# ui_cpu.net
KiCad netlist of a schematic drawn in Altium Designer
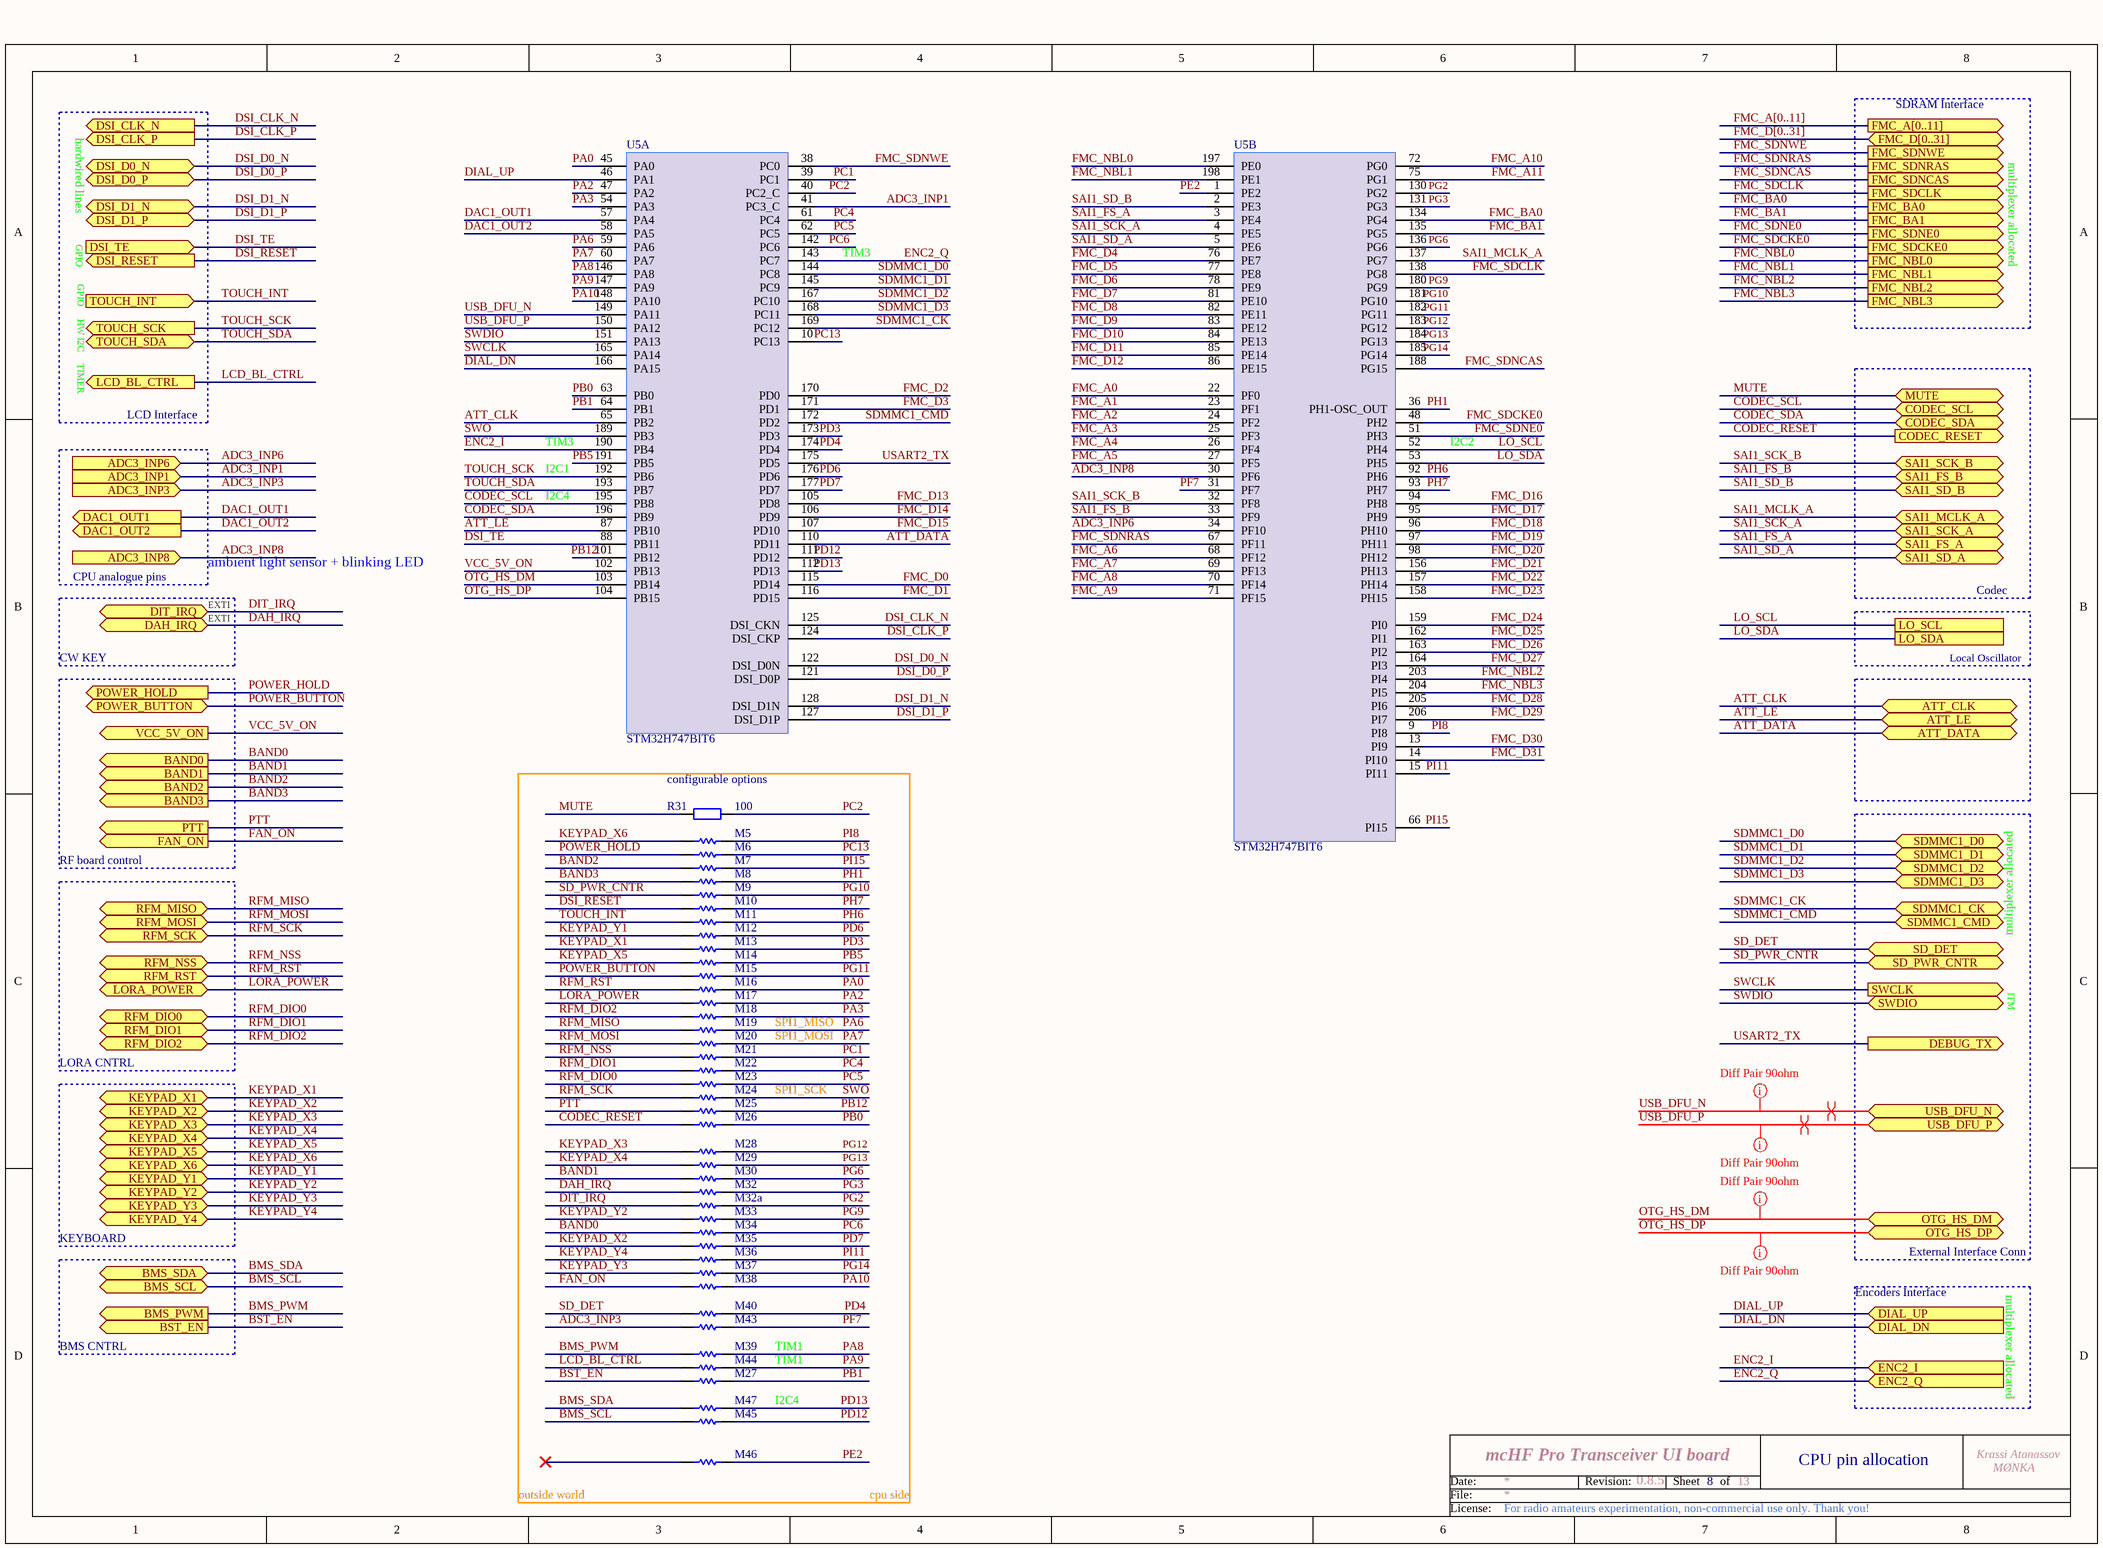
[diagram p0: ui_cpu.SchDoc]

(export (version "E")
  (design (tool "Eeschema 10.0.6"))
  (components
    (comp (ref "M5")
      (value "0")
      (footprint "SB_0603")
      (description "Link")
      (fields (field (name "PUBLISHER") "Altium Limited"))
      (libsource (lib "__ui") (part "Link"))
    )
    (comp (ref "M6")
      (value "0")
      (footprint "SB_0603")
      (description "Link")
      (fields (field (name "PUBLISHER") "Altium Limited"))
      (libsource (lib "__ui") (part "Link"))
    )
    (comp (ref "M7")
      (value "0")
      (footprint "SB_0603")
      (description "Link")
      (fields (field (name "PUBLISHER") "Altium Limited"))
      (libsource (lib "__ui") (part "Link"))
    )
    (comp (ref "M8")
      (value "0")
      (footprint "SB_0603")
      (description "Link")
      (fields (field (name "PUBLISHER") "Altium Limited"))
      (libsource (lib "__ui") (part "Link"))
    )
    (comp (ref "M9")
      (value "0")
      (footprint "SB_0603")
      (description "Link")
      (fields (field (name "PUBLISHER") "Altium Limited"))
      (libsource (lib "__ui") (part "Link"))
    )
    (comp (ref "M10")
      (value "0")
      (footprint "SB_0603")
      (description "Link")
      (fields (field (name "PUBLISHER") "Altium Limited"))
      (libsource (lib "__ui") (part "Link"))
    )
    (comp (ref "M11")
      (value "0")
      (footprint "SB_0603")
      (description "Link")
      (fields (field (name "PUBLISHER") "Altium Limited"))
      (libsource (lib "__ui") (part "Link"))
    )
    (comp (ref "M12")
      (value "0")
      (footprint "SB_0603")
      (description "Link")
      (fields (field (name "PUBLISHER") "Altium Limited"))
      (libsource (lib "__ui") (part "Link"))
    )
    (comp (ref "M13")
      (value "0")
      (footprint "SB_0603")
      (description "Link")
      (fields (field (name "PUBLISHER") "Altium Limited"))
      (libsource (lib "__ui") (part "Link"))
    )
    (comp (ref "M14")
      (value "0")
      (footprint "SB_0603")
      (description "Link")
      (fields (field (name "PUBLISHER") "Altium Limited"))
      (libsource (lib "__ui") (part "Link"))
    )
    (comp (ref "M15")
      (value "0")
      (footprint "SB_0603")
      (description "Link")
      (fields (field (name "PUBLISHER") "Altium Limited"))
      (libsource (lib "__ui") (part "Link"))
    )
    (comp (ref "M16")
      (value "0")
      (footprint "SB_0603")
      (description "Link")
      (fields (field (name "PUBLISHER") "Altium Limited"))
      (libsource (lib "__ui") (part "Link"))
    )
    (comp (ref "M17")
      (value "0")
      (footprint "SB_0603")
      (description "Link")
      (fields (field (name "PUBLISHER") "Altium Limited"))
      (libsource (lib "__ui") (part "Link"))
    )
    (comp (ref "M18")
      (value "0")
      (footprint "SB_0603")
      (description "Link")
      (fields (field (name "PUBLISHER") "Altium Limited"))
      (libsource (lib "__ui") (part "Link"))
    )
    (comp (ref "M19")
      (value "0")
      (footprint "SB_0603")
      (description "Link")
      (fields (field (name "PUBLISHER") "Altium Limited"))
      (libsource (lib "__ui") (part "Link"))
    )
    (comp (ref "M20")
      (value "0")
      (footprint "SB_0603")
      (description "Link")
      (fields (field (name "PUBLISHER") "Altium Limited"))
      (libsource (lib "__ui") (part "Link"))
    )
    (comp (ref "M21")
      (value "0")
      (footprint "SB_0603")
      (description "Link")
      (fields (field (name "PUBLISHER") "Altium Limited"))
      (libsource (lib "__ui") (part "Link"))
    )
    (comp (ref "M22")
      (value "0")
      (footprint "SB_0603")
      (description "Link")
      (fields (field (name "PUBLISHER") "Altium Limited"))
      (libsource (lib "__ui") (part "Link"))
    )
    (comp (ref "M23")
      (value "0")
      (footprint "SB_0603")
      (description "Link")
      (fields (field (name "PUBLISHER") "Altium Limited"))
      (libsource (lib "__ui") (part "Link"))
    )
    (comp (ref "M24")
      (value "0")
      (footprint "SB_0603")
      (description "Link")
      (fields (field (name "PUBLISHER") "Altium Limited"))
      (libsource (lib "__ui") (part "Link"))
    )
    (comp (ref "M25")
      (value "0")
      (footprint "SB_0603")
      (description "Link")
      (fields (field (name "PUBLISHER") "Altium Limited"))
      (libsource (lib "__ui") (part "Link"))
    )
    (comp (ref "M26")
      (value "0")
      (footprint "SB_0603")
      (description "Link")
      (fields (field (name "PUBLISHER") "Altium Limited"))
      (libsource (lib "__ui") (part "Link"))
    )
    (comp (ref "M27")
      (value "0")
      (footprint "SB_0603")
      (description "Link")
      (fields (field (name "PUBLISHER") "Altium Limited"))
      (libsource (lib "__ui") (part "Link"))
    )
    (comp (ref "M28")
      (value "0")
      (footprint "SB_0603")
      (description "Link")
      (fields (field (name "PUBLISHER") "Altium Limited"))
      (libsource (lib "__ui") (part "Link"))
    )
    (comp (ref "M29")
      (value "0")
      (footprint "SB_0603")
      (description "Link")
      (fields (field (name "PUBLISHER") "Altium Limited"))
      (libsource (lib "__ui") (part "Link"))
    )
    (comp (ref "M30")
      (value "0")
      (footprint "SB_0603")
      (description "Link")
      (fields (field (name "PUBLISHER") "Altium Limited"))
      (libsource (lib "__ui") (part "Link"))
    )
    (comp (ref "M32")
      (value "0")
      (footprint "SB_0603")
      (description "Link")
      (fields (field (name "PUBLISHER") "Altium Limited"))
      (libsource (lib "__ui") (part "Link"))
    )
    (comp (ref "M32a")
      (value "0")
      (footprint "SB_0603")
      (description "Link")
      (fields (field (name "PUBLISHER") "Altium Limited"))
      (libsource (lib "__ui") (part "Link"))
    )
    (comp (ref "M33")
      (value "0")
      (footprint "SB_0603")
      (description "Link")
      (fields (field (name "PUBLISHER") "Altium Limited"))
      (libsource (lib "__ui") (part "Link"))
    )
    (comp (ref "M34")
      (value "0")
      (footprint "SB_0603")
      (description "Link")
      (fields (field (name "PUBLISHER") "Altium Limited"))
      (libsource (lib "__ui") (part "Link"))
    )
    (comp (ref "M35")
      (value "0")
      (footprint "SB_0603")
      (description "Link")
      (fields (field (name "PUBLISHER") "Altium Limited"))
      (libsource (lib "__ui") (part "Link"))
    )
    (comp (ref "M36")
      (value "0")
      (footprint "SB_0603")
      (description "Link")
      (fields (field (name "PUBLISHER") "Altium Limited"))
      (libsource (lib "__ui") (part "Link"))
    )
    (comp (ref "M37")
      (value "0")
      (footprint "SB_0603")
      (description "Link")
      (fields (field (name "PUBLISHER") "Altium Limited"))
      (libsource (lib "__ui") (part "Link"))
    )
    (comp (ref "M38")
      (value "0")
      (footprint "SB_0603")
      (description "Link")
      (fields (field (name "PUBLISHER") "Altium Limited"))
      (libsource (lib "__ui") (part "Link"))
    )
    (comp (ref "M39")
      (value "0")
      (footprint "SB_0603")
      (description "Link")
      (fields (field (name "PUBLISHER") "Altium Limited"))
      (libsource (lib "__ui") (part "Link"))
    )
    (comp (ref "M40")
      (value "0")
      (footprint "SB_0603")
      (description "Link")
      (fields (field (name "PUBLISHER") "Altium Limited"))
      (libsource (lib "__ui") (part "Link"))
    )
    (comp (ref "M43")
      (value "0")
      (footprint "SB_0603")
      (description "Link")
      (fields (field (name "PUBLISHER") "Altium Limited"))
      (libsource (lib "__ui") (part "Link"))
    )
    (comp (ref "M44")
      (value "0")
      (footprint "SB_0603")
      (description "Link")
      (fields (field (name "PUBLISHER") "Altium Limited"))
      (libsource (lib "__ui") (part "Link"))
    )
    (comp (ref "M45")
      (value "0")
      (footprint "SB_0603")
      (description "Link")
      (fields (field (name "PUBLISHER") "Altium Limited"))
      (libsource (lib "__ui") (part "Link"))
    )
    (comp (ref "M46")
      (value "0")
      (footprint "SB_0603")
      (description "Link")
      (fields (field (name "PUBLISHER") "Altium Limited"))
      (libsource (lib "__ui") (part "Link"))
    )
    (comp (ref "M47")
      (value "0")
      (footprint "SB_0603")
      (description "Link")
      (fields (field (name "PUBLISHER") "Altium Limited"))
      (libsource (lib "__ui") (part "Link"))
    )
    (comp (ref "R31")
      (value "100")
      (footprint "0805")
      (description "Resistor")
      (libsource (lib "*") (part "RES"))
    )
    (comp (ref "U5")
      (value "STM32H747BIT6")
      (footprint "LQFP208-28x28x1.4")
      (description "STM32H747BIT6 LQFP208")
      (libsource (lib "__ui") (part "STM32H747BIT6"))
    )
  )
  (nets
    (net (code "1") (name "/ADC3_INP1") (class "Default")
      (node (ref "U5") (pin "41") (pinfunction "PC3_C_41") (pintype "passive"))
    )
    (net (code "2") (name "/ADC3_INP3") (class "Default")
      (node (ref "M43") (pin "1") (pinfunction "1_1") (pintype "passive"))
    )
    (net (code "3") (name "/ADC3_INP6") (class "Default")
      (node (ref "U5") (pin "34") (pinfunction "PF10_34") (pintype "passive"))
    )
    (net (code "4") (name "/ADC3_INP8") (class "Default")
      (node (ref "U5") (pin "30") (pinfunction "PF6_30") (pintype "passive"))
    )
    (net (code "5") (name "/ATT_CLK") (class "Default")
      (node (ref "U5") (pin "65") (pinfunction "PB2_65") (pintype "passive"))
    )
    (net (code "6") (name "/ATT_DATA") (class "Default")
      (node (ref "U5") (pin "110") (pinfunction "PD11_110") (pintype "passive"))
    )
    (net (code "7") (name "/ATT_LE") (class "Default")
      (node (ref "U5") (pin "87") (pinfunction "PB10_87") (pintype "passive"))
    )
    (net (code "8") (name "/BAND0") (class "Default")
      (node (ref "M34") (pin "1") (pinfunction "1_1") (pintype "passive"))
    )
    (net (code "9") (name "/BAND1") (class "Default")
      (node (ref "M30") (pin "1") (pinfunction "1_1") (pintype "passive"))
    )
    (net (code "10") (name "/BAND2") (class "Default")
      (node (ref "M7") (pin "1") (pinfunction "1_1") (pintype "passive"))
    )
    (net (code "11") (name "/BAND3") (class "Default")
      (node (ref "M8") (pin "1") (pinfunction "1_1") (pintype "passive"))
    )
    (net (code "12") (name "/BMS_PWM") (class "Default")
      (node (ref "M39") (pin "1") (pinfunction "1_1") (pintype "passive"))
    )
    (net (code "13") (name "/BMS_SCL") (class "Default")
      (node (ref "M45") (pin "1") (pinfunction "1_1") (pintype "passive"))
    )
    (net (code "14") (name "/BMS_SDA") (class "Default")
      (node (ref "M47") (pin "1") (pinfunction "1_1") (pintype "passive"))
    )
    (net (code "15") (name "/BST_EN") (class "Default")
      (node (ref "M27") (pin "1") (pinfunction "1_1") (pintype "passive"))
    )
    (net (code "16") (name "/CODEC_RESET") (class "Default")
      (node (ref "M26") (pin "1") (pinfunction "1_1") (pintype "passive"))
    )
    (net (code "17") (name "/CODEC_SCL") (class "Default")
      (node (ref "U5") (pin "195") (pinfunction "PB8_195") (pintype "passive"))
    )
    (net (code "18") (name "/CODEC_SDA") (class "Default")
      (node (ref "U5") (pin "196") (pinfunction "PB9_196") (pintype "passive"))
    )
    (net (code "19") (name "/DAC1_OUT1") (class "Default")
      (node (ref "U5") (pin "57") (pinfunction "PA4_57") (pintype "passive"))
    )
    (net (code "20") (name "/DAC1_OUT2") (class "Default")
      (node (ref "U5") (pin "58") (pinfunction "PA5_58") (pintype "passive"))
    )
    (net (code "21") (name "/DAH_IRQ") (class "Default")
      (node (ref "M32") (pin "1") (pinfunction "1_1") (pintype "passive"))
    )
    (net (code "22") (name "/DIAL_DN") (class "Default")
      (node (ref "U5") (pin "166") (pinfunction "PA15_166") (pintype "passive"))
    )
    (net (code "23") (name "/DIAL_UP") (class "Default")
      (node (ref "U5") (pin "46") (pinfunction "PA1_46") (pintype "passive"))
    )
    (net (code "24") (name "/DIT_IRQ") (class "Default")
      (node (ref "M32a") (pin "1") (pinfunction "1_1") (pintype "passive"))
    )
    (net (code "25") (name "/DSI_CLK_N") (class "Default")
      (node (ref "U5") (pin "125") (pinfunction "DSI_CKN_125") (pintype "passive"))
    )
    (net (code "26") (name "/DSI_CLK_P") (class "Default")
      (node (ref "U5") (pin "124") (pinfunction "DSI_CKP_124") (pintype "passive"))
    )
    (net (code "27") (name "/DSI_D0_N") (class "Default")
      (node (ref "U5") (pin "122") (pinfunction "DSI_D0N_122") (pintype "passive"))
    )
    (net (code "28") (name "/DSI_D0_P") (class "Default")
      (node (ref "U5") (pin "121") (pinfunction "DSI_D0P_121") (pintype "passive"))
    )
    (net (code "29") (name "/DSI_D1_N") (class "Default")
      (node (ref "U5") (pin "128") (pinfunction "DSI_D1N_128") (pintype "passive"))
    )
    (net (code "30") (name "/DSI_D1_P") (class "Default")
      (node (ref "U5") (pin "127") (pinfunction "DSI_D1P_127") (pintype "passive"))
    )
    (net (code "31") (name "/DSI_RESET") (class "Default")
      (node (ref "M10") (pin "1") (pinfunction "1_1") (pintype "passive"))
    )
    (net (code "32") (name "/DSI_TE") (class "Default")
      (node (ref "U5") (pin "88") (pinfunction "PB11_88") (pintype "passive"))
    )
    (net (code "33") (name "/ENC2_I") (class "Default")
      (node (ref "U5") (pin "190") (pinfunction "PB4_190") (pintype "passive"))
    )
    (net (code "34") (name "/ENC2_Q") (class "Default")
      (node (ref "U5") (pin "143") (pinfunction "PC7_143") (pintype "passive"))
    )
    (net (code "35") (name "/FAN_ON") (class "Default")
      (node (ref "M38") (pin "1") (pinfunction "1_1") (pintype "passive"))
    )
    (net (code "36") (name "/FMC_A0") (class "Default")
      (node (ref "U5") (pin "22") (pinfunction "PF0_22") (pintype "passive"))
    )
    (net (code "37") (name "/FMC_A1") (class "Default")
      (node (ref "U5") (pin "23") (pinfunction "PF1_23") (pintype "passive"))
    )
    (net (code "38") (name "/FMC_A2") (class "Default")
      (node (ref "U5") (pin "24") (pinfunction "PF2_24") (pintype "passive"))
    )
    (net (code "39") (name "/FMC_A3") (class "Default")
      (node (ref "U5") (pin "25") (pinfunction "PF3_25") (pintype "passive"))
    )
    (net (code "40") (name "/FMC_A4") (class "Default")
      (node (ref "U5") (pin "26") (pinfunction "PF4_26") (pintype "passive"))
    )
    (net (code "41") (name "/FMC_A5") (class "Default")
      (node (ref "U5") (pin "27") (pinfunction "PF5_27") (pintype "passive"))
    )
    (net (code "42") (name "/FMC_A6") (class "Default")
      (node (ref "U5") (pin "68") (pinfunction "PF12_68") (pintype "passive"))
    )
    (net (code "43") (name "/FMC_A7") (class "Default")
      (node (ref "U5") (pin "69") (pinfunction "PF13_69") (pintype "passive"))
    )
    (net (code "44") (name "/FMC_A8") (class "Default")
      (node (ref "U5") (pin "70") (pinfunction "PF14_70") (pintype "passive"))
    )
    (net (code "45") (name "/FMC_A9") (class "Default")
      (node (ref "U5") (pin "71") (pinfunction "PF15_71") (pintype "passive"))
    )
    (net (code "46") (name "/FMC_A10") (class "Default")
      (node (ref "U5") (pin "72") (pinfunction "PG0_72") (pintype "passive"))
    )
    (net (code "47") (name "/FMC_A11") (class "Default")
      (node (ref "U5") (pin "75") (pinfunction "PG1_75") (pintype "passive"))
    )
    (net (code "49") (name "/FMC_BA0") (class "Default")
      (node (ref "U5") (pin "134") (pinfunction "PG4_134") (pintype "passive"))
    )
    (net (code "50") (name "/FMC_BA1") (class "Default")
      (node (ref "U5") (pin "135") (pinfunction "PG5_135") (pintype "passive"))
    )
    (net (code "51") (name "/FMC_D0") (class "Default")
      (node (ref "U5") (pin "115") (pinfunction "PD14_115") (pintype "passive"))
    )
    (net (code "52") (name "/FMC_D1") (class "Default")
      (node (ref "U5") (pin "116") (pinfunction "PD15_116") (pintype "passive"))
    )
    (net (code "53") (name "/FMC_D2") (class "Default")
      (node (ref "U5") (pin "170") (pinfunction "PD0_170") (pintype "passive"))
    )
    (net (code "54") (name "/FMC_D3") (class "Default")
      (node (ref "U5") (pin "171") (pinfunction "PD1_171") (pintype "passive"))
    )
    (net (code "55") (name "/FMC_D4") (class "Default")
      (node (ref "U5") (pin "76") (pinfunction "PE7_76") (pintype "passive"))
    )
    (net (code "56") (name "/FMC_D5") (class "Default")
      (node (ref "U5") (pin "77") (pinfunction "PE8_77") (pintype "passive"))
    )
    (net (code "57") (name "/FMC_D6") (class "Default")
      (node (ref "U5") (pin "78") (pinfunction "PE9_78") (pintype "passive"))
    )
    (net (code "58") (name "/FMC_D7") (class "Default")
      (node (ref "U5") (pin "81") (pinfunction "PE10_81") (pintype "passive"))
    )
    (net (code "59") (name "/FMC_D8") (class "Default")
      (node (ref "U5") (pin "82") (pinfunction "PE11_82") (pintype "passive"))
    )
    (net (code "60") (name "/FMC_D9") (class "Default")
      (node (ref "U5") (pin "83") (pinfunction "PE12_83") (pintype "passive"))
    )
    (net (code "61") (name "/FMC_D10") (class "Default")
      (node (ref "U5") (pin "84") (pinfunction "PE13_84") (pintype "passive"))
    )
    (net (code "62") (name "/FMC_D11") (class "Default")
      (node (ref "U5") (pin "85") (pinfunction "PE14_85") (pintype "passive"))
    )
    (net (code "63") (name "/FMC_D12") (class "Default")
      (node (ref "U5") (pin "86") (pinfunction "PE15_86") (pintype "passive"))
    )
    (net (code "64") (name "/FMC_D13") (class "Default")
      (node (ref "U5") (pin "105") (pinfunction "PD8_105") (pintype "passive"))
    )
    (net (code "65") (name "/FMC_D14") (class "Default")
      (node (ref "U5") (pin "106") (pinfunction "PD9_106") (pintype "passive"))
    )
    (net (code "66") (name "/FMC_D15") (class "Default")
      (node (ref "U5") (pin "107") (pinfunction "PD10_107") (pintype "passive"))
    )
    (net (code "67") (name "/FMC_D16") (class "Default")
      (node (ref "U5") (pin "94") (pinfunction "PH8_94") (pintype "passive"))
    )
    (net (code "68") (name "/FMC_D17") (class "Default")
      (node (ref "U5") (pin "95") (pinfunction "PH9_95") (pintype "passive"))
    )
    (net (code "69") (name "/FMC_D18") (class "Default")
      (node (ref "U5") (pin "96") (pinfunction "PH10_96") (pintype "passive"))
    )
    (net (code "70") (name "/FMC_D19") (class "Default")
      (node (ref "U5") (pin "97") (pinfunction "PH11_97") (pintype "passive"))
    )
    (net (code "71") (name "/FMC_D20") (class "Default")
      (node (ref "U5") (pin "98") (pinfunction "PH12_98") (pintype "passive"))
    )
    (net (code "72") (name "/FMC_D21") (class "Default")
      (node (ref "U5") (pin "156") (pinfunction "PH13_156") (pintype "passive"))
    )
    (net (code "73") (name "/FMC_D22") (class "Default")
      (node (ref "U5") (pin "157") (pinfunction "PH14_157") (pintype "passive"))
    )
    (net (code "74") (name "/FMC_D23") (class "Default")
      (node (ref "U5") (pin "158") (pinfunction "PH15_158") (pintype "passive"))
    )
    (net (code "75") (name "/FMC_D24") (class "Default")
      (node (ref "U5") (pin "159") (pinfunction "PI0_159") (pintype "passive"))
    )
    (net (code "76") (name "/FMC_D25") (class "Default")
      (node (ref "U5") (pin "162") (pinfunction "PI1_162") (pintype "passive"))
    )
    (net (code "77") (name "/FMC_D26") (class "Default")
      (node (ref "U5") (pin "163") (pinfunction "PI2_163") (pintype "passive"))
    )
    (net (code "78") (name "/FMC_D27") (class "Default")
      (node (ref "U5") (pin "164") (pinfunction "PI3_164") (pintype "passive"))
    )
    (net (code "79") (name "/FMC_D28") (class "Default")
      (node (ref "U5") (pin "205") (pinfunction "PI6_205") (pintype "passive"))
    )
    (net (code "80") (name "/FMC_D29") (class "Default")
      (node (ref "U5") (pin "206") (pinfunction "PI7_206") (pintype "passive"))
    )
    (net (code "81") (name "/FMC_D30") (class "Default")
      (node (ref "U5") (pin "13") (pinfunction "PI9_13") (pintype "passive"))
    )
    (net (code "82") (name "/FMC_D31") (class "Default")
      (node (ref "U5") (pin "14") (pinfunction "PI10_14") (pintype "passive"))
    )
    (net (code "84") (name "/FMC_NBL0") (class "Default")
      (node (ref "U5") (pin "197") (pinfunction "PE0_197") (pintype "passive"))
    )
    (net (code "85") (name "/FMC_NBL1") (class "Default")
      (node (ref "U5") (pin "198") (pinfunction "PE1_198") (pintype "passive"))
    )
    (net (code "86") (name "/FMC_NBL2") (class "Default")
      (node (ref "U5") (pin "203") (pinfunction "PI4_203") (pintype "passive"))
    )
    (net (code "87") (name "/FMC_NBL3") (class "Default")
      (node (ref "U5") (pin "204") (pinfunction "PI5_204") (pintype "passive"))
    )
    (net (code "88") (name "/FMC_SDCKE0") (class "Default")
      (node (ref "U5") (pin "48") (pinfunction "PH2_48") (pintype "passive"))
    )
    (net (code "89") (name "/FMC_SDCLK") (class "Default")
      (node (ref "U5") (pin "138") (pinfunction "PG8_138") (pintype "passive"))
    )
    (net (code "90") (name "/FMC_SDNCAS") (class "Default")
      (node (ref "U5") (pin "188") (pinfunction "PG15_188") (pintype "passive"))
    )
    (net (code "91") (name "/FMC_SDNE0") (class "Default")
      (node (ref "U5") (pin "51") (pinfunction "PH3_51") (pintype "passive"))
    )
    (net (code "92") (name "/FMC_SDNRAS") (class "Default")
      (node (ref "U5") (pin "67") (pinfunction "PF11_67") (pintype "passive"))
    )
    (net (code "93") (name "/FMC_SDNWE") (class "Default")
      (node (ref "U5") (pin "38") (pinfunction "PC0_38") (pintype "passive"))
    )
    (net (code "94") (name "/KEYPAD_X1") (class "Default")
      (node (ref "M13") (pin "1") (pinfunction "1_1") (pintype "passive"))
    )
    (net (code "95") (name "/KEYPAD_X2") (class "Default")
      (node (ref "M35") (pin "1") (pinfunction "1_1") (pintype "passive"))
    )
    (net (code "96") (name "/KEYPAD_X3") (class "Default")
      (node (ref "M28") (pin "1") (pinfunction "1_1") (pintype "passive"))
    )
    (net (code "97") (name "/KEYPAD_X4") (class "Default")
      (node (ref "M29") (pin "1") (pinfunction "1_1") (pintype "passive"))
    )
    (net (code "98") (name "/KEYPAD_X5") (class "Default")
      (node (ref "M14") (pin "1") (pinfunction "1_1") (pintype "passive"))
    )
    (net (code "99") (name "/KEYPAD_X6") (class "Default")
      (node (ref "M5") (pin "1") (pinfunction "1_1") (pintype "passive"))
    )
    (net (code "100") (name "/KEYPAD_Y1") (class "Default")
      (node (ref "M12") (pin "1") (pinfunction "1_1") (pintype "passive"))
    )
    (net (code "101") (name "/KEYPAD_Y2") (class "Default")
      (node (ref "M33") (pin "1") (pinfunction "1_1") (pintype "passive"))
    )
    (net (code "102") (name "/KEYPAD_Y3") (class "Default")
      (node (ref "M37") (pin "1") (pinfunction "1_1") (pintype "passive"))
    )
    (net (code "103") (name "/KEYPAD_Y4") (class "Default")
      (node (ref "M36") (pin "1") (pinfunction "1_1") (pintype "passive"))
    )
    (net (code "104") (name "/LCD_BL_CTRL") (class "Default")
      (node (ref "M44") (pin "1") (pinfunction "1_1") (pintype "passive"))
    )
    (net (code "105") (name "/LORA_POWER") (class "Default")
      (node (ref "M17") (pin "1") (pinfunction "1_1") (pintype "passive"))
    )
    (net (code "106") (name "/LO_SCL") (class "Default")
      (node (ref "U5") (pin "52") (pinfunction "PH4_52") (pintype "passive"))
    )
    (net (code "107") (name "/LO_SDA") (class "Default")
      (node (ref "U5") (pin "53") (pinfunction "PH5_53") (pintype "passive"))
    )
    (net (code "108") (name "/MUTE") (class "Default")
      (node (ref "R31") (pin "2") (pinfunction "2_2") (pintype "passive"))
    )
    (net (code "109") (name "/OTG_HS_DM") (class "Default")
      (node (ref "U5") (pin "103") (pinfunction "PB14_103") (pintype "passive"))
    )
    (net (code "110") (name "/OTG_HS_DP") (class "Default")
      (node (ref "U5") (pin "104") (pinfunction "PB15_104") (pintype "passive"))
    )
    (net (code "111") (name "/PA0") (class "Default")
      (node (ref "M16") (pin "2") (pinfunction "2_2") (pintype "passive"))
      (node (ref "U5") (pin "45") (pinfunction "PA0_45") (pintype "passive"))
    )
    (net (code "112") (name "/PA2") (class "Default")
      (node (ref "M17") (pin "2") (pinfunction "2_2") (pintype "passive"))
      (node (ref "U5") (pin "47") (pinfunction "PA2_47") (pintype "passive"))
    )
    (net (code "113") (name "/PA3") (class "Default")
      (node (ref "M18") (pin "2") (pinfunction "2_2") (pintype "passive"))
      (node (ref "U5") (pin "54") (pinfunction "PA3_54") (pintype "passive"))
    )
    (net (code "114") (name "/PA6") (class "Default")
      (node (ref "M19") (pin "2") (pinfunction "2_2") (pintype "passive"))
      (node (ref "U5") (pin "59") (pinfunction "PA6_59") (pintype "passive"))
    )
    (net (code "115") (name "/PA7") (class "Default")
      (node (ref "M20") (pin "2") (pinfunction "2_2") (pintype "passive"))
      (node (ref "U5") (pin "60") (pinfunction "PA7_60") (pintype "passive"))
    )
    (net (code "116") (name "/PA8") (class "Default")
      (node (ref "M39") (pin "2") (pinfunction "2_2") (pintype "passive"))
      (node (ref "U5") (pin "146") (pinfunction "PA8_146") (pintype "passive"))
    )
    (net (code "117") (name "/PA9") (class "Default")
      (node (ref "M44") (pin "2") (pinfunction "2_2") (pintype "passive"))
      (node (ref "U5") (pin "147") (pinfunction "PA9_147") (pintype "passive"))
    )
    (net (code "118") (name "/PA10") (class "Default")
      (node (ref "M38") (pin "2") (pinfunction "2_2") (pintype "passive"))
      (node (ref "U5") (pin "148") (pinfunction "PA10_148") (pintype "passive"))
    )
    (net (code "119") (name "/PB0") (class "Default")
      (node (ref "M26") (pin "2") (pinfunction "2_2") (pintype "passive"))
      (node (ref "U5") (pin "63") (pinfunction "PB0_63") (pintype "passive"))
    )
    (net (code "120") (name "/PB1") (class "Default")
      (node (ref "M27") (pin "2") (pinfunction "2_2") (pintype "passive"))
      (node (ref "U5") (pin "64") (pinfunction "PB1_64") (pintype "passive"))
    )
    (net (code "121") (name "/PB5") (class "Default")
      (node (ref "M14") (pin "2") (pinfunction "2_2") (pintype "passive"))
      (node (ref "U5") (pin "191") (pinfunction "PB5_191") (pintype "passive"))
    )
    (net (code "122") (name "/PB12") (class "Default")
      (node (ref "M25") (pin "2") (pinfunction "2_2") (pintype "passive"))
      (node (ref "U5") (pin "101") (pinfunction "PB12_101") (pintype "passive"))
    )
    (net (code "123") (name "/PC1") (class "Default")
      (node (ref "M21") (pin "2") (pinfunction "2_2") (pintype "passive"))
      (node (ref "U5") (pin "39") (pinfunction "PC1_39") (pintype "passive"))
    )
    (net (code "124") (name "/PC2") (class "Default")
      (node (ref "R31") (pin "1") (pinfunction "1_1") (pintype "passive"))
      (node (ref "U5") (pin "40") (pinfunction "PC2_C_40") (pintype "passive"))
    )
    (net (code "125") (name "/PC4") (class "Default")
      (node (ref "M22") (pin "2") (pinfunction "2_2") (pintype "passive"))
      (node (ref "U5") (pin "61") (pinfunction "PC4_61") (pintype "passive"))
    )
    (net (code "126") (name "/PC5") (class "Default")
      (node (ref "M23") (pin "2") (pinfunction "2_2") (pintype "passive"))
      (node (ref "U5") (pin "62") (pinfunction "PC5_62") (pintype "passive"))
    )
    (net (code "127") (name "/PC6") (class "Default")
      (node (ref "M34") (pin "2") (pinfunction "2_2") (pintype "passive"))
      (node (ref "U5") (pin "142") (pinfunction "PC6_142") (pintype "passive"))
    )
    (net (code "128") (name "/PC13") (class "Default")
      (node (ref "M6") (pin "2") (pinfunction "2_2") (pintype "passive"))
      (node (ref "U5") (pin "10") (pinfunction "PC13_10") (pintype "passive"))
    )
    (net (code "129") (name "/PD3") (class "Default")
      (node (ref "M13") (pin "2") (pinfunction "2_2") (pintype "passive"))
      (node (ref "U5") (pin "173") (pinfunction "PD3_173") (pintype "passive"))
    )
    (net (code "130") (name "/PD4") (class "Default")
      (node (ref "M40") (pin "2") (pinfunction "2_2") (pintype "passive"))
      (node (ref "U5") (pin "174") (pinfunction "PD4_174") (pintype "passive"))
    )
    (net (code "131") (name "/PD6") (class "Default")
      (node (ref "M12") (pin "2") (pinfunction "2_2") (pintype "passive"))
      (node (ref "U5") (pin "176") (pinfunction "PD6_176") (pintype "passive"))
    )
    (net (code "132") (name "/PD7") (class "Default")
      (node (ref "M35") (pin "2") (pinfunction "2_2") (pintype "passive"))
      (node (ref "U5") (pin "177") (pinfunction "PD7_177") (pintype "passive"))
    )
    (net (code "133") (name "/PD12") (class "Default")
      (node (ref "M45") (pin "2") (pinfunction "2_2") (pintype "passive"))
      (node (ref "U5") (pin "111") (pinfunction "PD12_111") (pintype "passive"))
    )
    (net (code "134") (name "/PD13") (class "Default")
      (node (ref "M47") (pin "2") (pinfunction "2_2") (pintype "passive"))
      (node (ref "U5") (pin "112") (pinfunction "PD13_112") (pintype "passive"))
    )
    (net (code "135") (name "/PE2") (class "Default")
      (node (ref "M46") (pin "2") (pinfunction "2_2") (pintype "passive"))
      (node (ref "U5") (pin "1") (pinfunction "PE2_1") (pintype "passive"))
    )
    (net (code "136") (name "/PF7") (class "Default")
      (node (ref "M43") (pin "2") (pinfunction "2_2") (pintype "passive"))
      (node (ref "U5") (pin "31") (pinfunction "PF7_31") (pintype "passive"))
    )
    (net (code "137") (name "/PG2") (class "Default")
      (node (ref "M32a") (pin "2") (pinfunction "2_2") (pintype "passive"))
      (node (ref "U5") (pin "130") (pinfunction "PG2_130") (pintype "passive"))
    )
    (net (code "138") (name "/PG3") (class "Default")
      (node (ref "M32") (pin "2") (pinfunction "2_2") (pintype "passive"))
      (node (ref "U5") (pin "131") (pinfunction "PG3_131") (pintype "passive"))
    )
    (net (code "139") (name "/PG6") (class "Default")
      (node (ref "M30") (pin "2") (pinfunction "2_2") (pintype "passive"))
      (node (ref "U5") (pin "136") (pinfunction "PG6_136") (pintype "passive"))
    )
    (net (code "140") (name "/PG9") (class "Default")
      (node (ref "M33") (pin "2") (pinfunction "2_2") (pintype "passive"))
      (node (ref "U5") (pin "180") (pinfunction "PG9_180") (pintype "passive"))
    )
    (net (code "141") (name "/PG10") (class "Default")
      (node (ref "M9") (pin "2") (pinfunction "2_2") (pintype "passive"))
      (node (ref "U5") (pin "181") (pinfunction "PG10_181") (pintype "passive"))
    )
    (net (code "142") (name "/PG11") (class "Default")
      (node (ref "M15") (pin "2") (pinfunction "2_2") (pintype "passive"))
      (node (ref "U5") (pin "182") (pinfunction "PG11_182") (pintype "passive"))
    )
    (net (code "143") (name "/PG12") (class "Default")
      (node (ref "M28") (pin "2") (pinfunction "2_2") (pintype "passive"))
      (node (ref "U5") (pin "183") (pinfunction "PG12_183") (pintype "passive"))
    )
    (net (code "144") (name "/PG13") (class "Default")
      (node (ref "M29") (pin "2") (pinfunction "2_2") (pintype "passive"))
      (node (ref "U5") (pin "184") (pinfunction "PG13_184") (pintype "passive"))
    )
    (net (code "145") (name "/PG14") (class "Default")
      (node (ref "M37") (pin "2") (pinfunction "2_2") (pintype "passive"))
      (node (ref "U5") (pin "185") (pinfunction "PG14_185") (pintype "passive"))
    )
    (net (code "146") (name "/PH1") (class "Default")
      (node (ref "M8") (pin "2") (pinfunction "2_2") (pintype "passive"))
      (node (ref "U5") (pin "36") (pinfunction "PH1-OSC_OUT_36") (pintype "passive"))
    )
    (net (code "147") (name "/PH6") (class "Default")
      (node (ref "M11") (pin "2") (pinfunction "2_2") (pintype "passive"))
      (node (ref "U5") (pin "92") (pinfunction "PH6_92") (pintype "passive"))
    )
    (net (code "148") (name "/PH7") (class "Default")
      (node (ref "M10") (pin "2") (pinfunction "2_2") (pintype "passive"))
      (node (ref "U5") (pin "93") (pinfunction "PH7_93") (pintype "passive"))
    )
    (net (code "149") (name "/PI8") (class "Default")
      (node (ref "M5") (pin "2") (pinfunction "2_2") (pintype "passive"))
      (node (ref "U5") (pin "9") (pinfunction "PI8_9") (pintype "passive"))
    )
    (net (code "150") (name "/PI11") (class "Default")
      (node (ref "M36") (pin "2") (pinfunction "2_2") (pintype "passive"))
      (node (ref "U5") (pin "15") (pinfunction "PI11_15") (pintype "passive"))
    )
    (net (code "151") (name "/PI15") (class "Default")
      (node (ref "M7") (pin "2") (pinfunction "2_2") (pintype "passive"))
      (node (ref "U5") (pin "66") (pinfunction "PI15_66") (pintype "passive"))
    )
    (net (code "152") (name "/POWER_BUTTON") (class "Default")
      (node (ref "M15") (pin "1") (pinfunction "1_1") (pintype "passive"))
    )
    (net (code "153") (name "/POWER_HOLD") (class "Default")
      (node (ref "M6") (pin "1") (pinfunction "1_1") (pintype "passive"))
    )
    (net (code "154") (name "/PTT") (class "Default")
      (node (ref "M25") (pin "1") (pinfunction "1_1") (pintype "passive"))
    )
    (net (code "155") (name "/RFM_DIO0") (class "Default")
      (node (ref "M23") (pin "1") (pinfunction "1_1") (pintype "passive"))
    )
    (net (code "156") (name "/RFM_DIO1") (class "Default")
      (node (ref "M22") (pin "1") (pinfunction "1_1") (pintype "passive"))
    )
    (net (code "157") (name "/RFM_DIO2") (class "Default")
      (node (ref "M18") (pin "1") (pinfunction "1_1") (pintype "passive"))
    )
    (net (code "158") (name "/RFM_MISO") (class "Default")
      (node (ref "M19") (pin "1") (pinfunction "1_1") (pintype "passive"))
    )
    (net (code "159") (name "/RFM_MOSI") (class "Default")
      (node (ref "M20") (pin "1") (pinfunction "1_1") (pintype "passive"))
    )
    (net (code "160") (name "/RFM_NSS") (class "Default")
      (node (ref "M21") (pin "1") (pinfunction "1_1") (pintype "passive"))
    )
    (net (code "161") (name "/RFM_RST") (class "Default")
      (node (ref "M16") (pin "1") (pinfunction "1_1") (pintype "passive"))
    )
    (net (code "162") (name "/RFM_SCK") (class "Default")
      (node (ref "M24") (pin "1") (pinfunction "1_1") (pintype "passive"))
    )
    (net (code "163") (name "/SAI1_FS_A") (class "Default")
      (node (ref "U5") (pin "3") (pinfunction "PE4_3") (pintype "passive"))
    )
    (net (code "164") (name "/SAI1_FS_B") (class "Default")
      (node (ref "U5") (pin "33") (pinfunction "PF9_33") (pintype "passive"))
    )
    (net (code "165") (name "/SAI1_MCLK_A") (class "Default")
      (node (ref "U5") (pin "137") (pinfunction "PG7_137") (pintype "passive"))
    )
    (net (code "166") (name "/SAI1_SCK_A") (class "Default")
      (node (ref "U5") (pin "4") (pinfunction "PE5_4") (pintype "passive"))
    )
    (net (code "167") (name "/SAI1_SCK_B") (class "Default")
      (node (ref "U5") (pin "32") (pinfunction "PF8_32") (pintype "passive"))
    )
    (net (code "168") (name "/SAI1_SD_A") (class "Default")
      (node (ref "U5") (pin "5") (pinfunction "PE6_5") (pintype "passive"))
    )
    (net (code "169") (name "/SAI1_SD_B") (class "Default")
      (node (ref "U5") (pin "2") (pinfunction "PE3_2") (pintype "passive"))
    )
    (net (code "170") (name "/SDMMC1_CK") (class "Default")
      (node (ref "U5") (pin "169") (pinfunction "PC12_169") (pintype "passive"))
    )
    (net (code "171") (name "/SDMMC1_CMD") (class "Default")
      (node (ref "U5") (pin "172") (pinfunction "PD2_172") (pintype "passive"))
    )
    (net (code "172") (name "/SDMMC1_D0") (class "Default")
      (node (ref "U5") (pin "144") (pinfunction "PC8_144") (pintype "passive"))
    )
    (net (code "173") (name "/SDMMC1_D1") (class "Default")
      (node (ref "U5") (pin "145") (pinfunction "PC9_145") (pintype "passive"))
    )
    (net (code "174") (name "/SDMMC1_D2") (class "Default")
      (node (ref "U5") (pin "167") (pinfunction "PC10_167") (pintype "passive"))
    )
    (net (code "175") (name "/SDMMC1_D3") (class "Default")
      (node (ref "U5") (pin "168") (pinfunction "PC11_168") (pintype "passive"))
    )
    (net (code "176") (name "/SD_DET") (class "Default")
      (node (ref "M40") (pin "1") (pinfunction "1_1") (pintype "passive"))
    )
    (net (code "177") (name "/SD_PWR_CNTR") (class "Default")
      (node (ref "M9") (pin "1") (pinfunction "1_1") (pintype "passive"))
    )
    (net (code "178") (name "/SWCLK") (class "Default")
      (node (ref "U5") (pin "165") (pinfunction "PA14_165") (pintype "passive"))
    )
    (net (code "179") (name "/SWDIO") (class "Default")
      (node (ref "U5") (pin "151") (pinfunction "PA13_151") (pintype "passive"))
    )
    (net (code "180") (name "/SWO") (class "Default")
      (node (ref "M24") (pin "2") (pinfunction "2_2") (pintype "passive"))
      (node (ref "U5") (pin "189") (pinfunction "PB3_189") (pintype "passive"))
    )
    (net (code "181") (name "/TOUCH_INT") (class "Default")
      (node (ref "M11") (pin "1") (pinfunction "1_1") (pintype "passive"))
    )
    (net (code "182") (name "/TOUCH_SCK") (class "Default")
      (node (ref "U5") (pin "192") (pinfunction "PB6_192") (pintype "passive"))
    )
    (net (code "183") (name "/TOUCH_SDA") (class "Default")
      (node (ref "U5") (pin "193") (pinfunction "PB7_193") (pintype "passive"))
    )
    (net (code "184") (name "/USART2_TX") (class "Default")
      (node (ref "U5") (pin "175") (pinfunction "PD5_175") (pintype "passive"))
    )
    (net (code "185") (name "/USB_DFU_N") (class "Default")
      (node (ref "U5") (pin "149") (pinfunction "PA11_149") (pintype "passive"))
    )
    (net (code "186") (name "/USB_DFU_P") (class "Default")
      (node (ref "U5") (pin "150") (pinfunction "PA12_150") (pintype "passive"))
    )
    (net (code "187") (name "/VCC_5V_ON") (class "Default")
      (node (ref "U5") (pin "102") (pinfunction "PB13_102") (pintype "passive"))
    )
    (net (code "188") (name "unconnected-(M46-Pad1)") (class "Default")
      (node (ref "M46") (pin "1") (pinfunction "1_1") (pintype "passive+no_connect"))
    )
  )
)
